# V_FB.net
KiCad netlist of a schematic drawn in Altium Designer
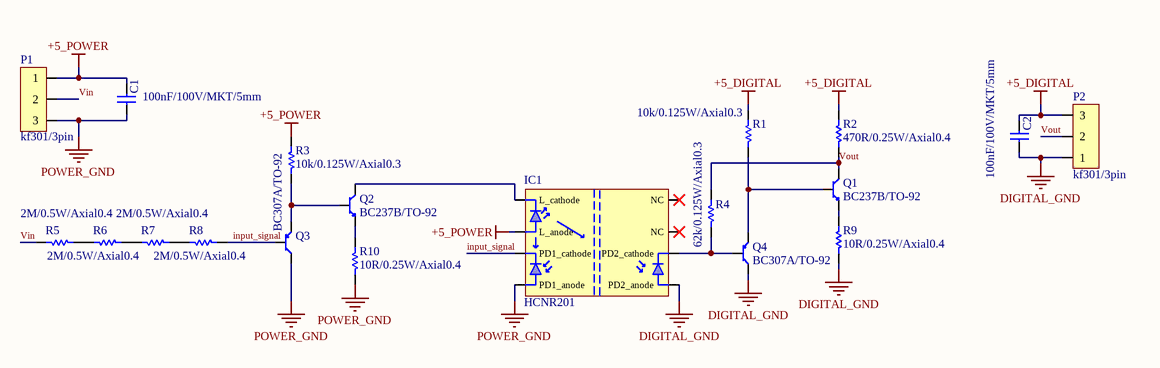
[diagram p0: V_FB.SchDoc]

(export (version "E")
  (design (tool "Eeschema 10.0.6"))
  (components
    (comp (ref "C1")
      (value "100nF/100V/MKT/5mm")
      (footprint "mkt 5mm")
      (description "Capacitor")
      (libsource (lib "Schlib") (part "Capacitor"))
    )
    (comp (ref "C2")
      (value "100nF/100V/MKT/5mm")
      (footprint "mkt 5mm")
      (description "Capacitor")
      (libsource (lib "Schlib") (part "Capacitor"))
    )
    (comp (ref "IC1")
      (value "HCNR201")
      (footprint "HCNR201_DIP8")
      (description "isolate linear optocoupler")
      (libsource (lib "Schlib1") (part "HCNR201"))
    )
    (comp (ref "P1")
      (value "kf301/3pin")
      (footprint "kf301/3pin")
      (description "RELAY")
      (fields (field (name "PUBLISHER") "Altium Limited"))
      (libsource (lib "") (part "kf301/3pin_1"))
    )
    (comp (ref "P2")
      (value "kf301/3pin")
      (footprint "kf301/3pin")
      (description "RELAY")
      (fields (field (name "PUBLISHER") "Altium Limited"))
      (libsource (lib "Schlib1") (part "kf301/3pin"))
    )
    (comp (ref "Q1")
      (value "BC237B/TO-92")
      (footprint "TO-92")
      (description "npn")
      (libsource (lib "Schlib1") (part "BC237B"))
    )
    (comp (ref "Q2")
      (value "BC237B/TO-92")
      (footprint "TO-92")
      (description "npn")
      (libsource (lib "Schlib1") (part "BC237B"))
    )
    (comp (ref "Q3")
      (value "BC307A/TO-92")
      (footprint "TO-92")
      (description "pnp")
      (libsource (lib "Schlib1") (part "BC307A"))
    )
    (comp (ref "Q4")
      (value "BC307A/TO-92")
      (footprint "TO-92")
      (description "pnp")
      (libsource (lib "Schlib1") (part "BC307A"))
    )
    (comp (ref "R1")
      (value "10k/0.125W/Axial0.3")
      (footprint "Axial 0.3")
      (description "Resistor")
      (fields (field (name "PUBLISHER") "Altium Limited"))
      (libsource (lib "Schlib1") (part "Res"))
    )
    (comp (ref "R2")
      (value "470R/0.25W/Axial0.4")
      (footprint "Axial 0.4")
      (description "Resistor")
      (fields (field (name "PUBLISHER") "Altium Limited"))
      (libsource (lib "Schlib1") (part "Res"))
    )
    (comp (ref "R3")
      (value "10k/0.125W/Axial0.3")
      (footprint "Axial 0.3")
      (description "Resistor")
      (fields (field (name "PUBLISHER") "Altium Limited"))
      (libsource (lib "Schlib1") (part "Res"))
    )
    (comp (ref "R4")
      (value "62k/0.125W/Axial0.3")
      (footprint "Axial 0.3")
      (description "Resistor")
      (fields (field (name "PUBLISHER") "Altium Limited"))
      (libsource (lib "Schlib1") (part "Res"))
    )
    (comp (ref "R5")
      (value "2M/0.5W/Axial0.4")
      (footprint "Axial 0.4")
      (description "Resistor")
      (fields (field (name "PUBLISHER") "Altium Limited"))
      (libsource (lib "Schlib1") (part "Res"))
    )
    (comp (ref "R6")
      (value "2M/0.5W/Axial0.4")
      (footprint "Axial 0.4")
      (description "Resistor")
      (fields (field (name "PUBLISHER") "Altium Limited"))
      (libsource (lib "Schlib1") (part "Res"))
    )
    (comp (ref "R7")
      (value "2M/0.5W/Axial0.4")
      (footprint "Axial 0.4")
      (description "Resistor")
      (fields (field (name "PUBLISHER") "Altium Limited"))
      (libsource (lib "Schlib1") (part "Res"))
    )
    (comp (ref "R8")
      (value "2M/0.5W/Axial0.4")
      (footprint "Axial 0.4")
      (description "Resistor")
      (fields (field (name "PUBLISHER") "Altium Limited"))
      (libsource (lib "Schlib1") (part "Res"))
    )
    (comp (ref "R9")
      (value "10R/0.25W/Axial0.4")
      (footprint "Axial 0.4")
      (description "Resistor")
      (fields (field (name "PUBLISHER") "Altium Limited"))
      (libsource (lib "Schlib1") (part "Res"))
    )
    (comp (ref "R10")
      (value "10R/0.25W/Axial0.4")
      (footprint "Axial 0.4")
      (description "Resistor")
      (fields (field (name "PUBLISHER") "Altium Limited"))
      (libsource (lib "Schlib1") (part "Res"))
    )
  )
  (nets
    (net (code "1") (name "+5_DIGITAL") (class "Default")
      (node (ref "C2") (pin "2") (pinfunction "-_2") (pintype "passive"))
      (node (ref "P2") (pin "3") (pinfunction "3_3") (pintype "passive"))
      (node (ref "R1") (pin "1") (pinfunction "1_1") (pintype "passive"))
      (node (ref "R2") (pin "1") (pinfunction "1_1") (pintype "passive"))
    )
    (net (code "2") (name "+5_POWER") (class "Default")
      (node (ref "C1") (pin "2") (pinfunction "-_2") (pintype "passive"))
      (node (ref "IC1") (pin "2") (pinfunction "L_anode_2") (pintype "passive"))
      (node (ref "P1") (pin "1") (pinfunction "1_1") (pintype "passive"))
      (node (ref "R3") (pin "1") (pinfunction "1_1") (pintype "passive"))
    )
    (net (code "3") (name "/Vin") (class "Default")
      (node (ref "P1") (pin "2") (pinfunction "2_2") (pintype "passive"))
      (node (ref "R5") (pin "1") (pinfunction "1_1") (pintype "passive"))
    )
    (net (code "4") (name "/Vout") (class "Default")
      (node (ref "P2") (pin "2") (pinfunction "2_2") (pintype "passive"))
      (node (ref "Q1") (pin "1") (pinfunction "C_1") (pintype "passive"))
      (node (ref "R2") (pin "2") (pinfunction "2_2") (pintype "passive"))
      (node (ref "R4") (pin "2") (pinfunction "2_2") (pintype "passive"))
    )
    (net (code "5") (name "/input_signal") (class "Default")
      (node (ref "IC1") (pin "3") (pinfunction "PD1_cathode_3") (pintype "passive"))
      (node (ref "Q3") (pin "2") (pinfunction "B_2") (pintype "passive"))
      (node (ref "R8") (pin "2") (pinfunction "2_2") (pintype "passive"))
    )
    (net (code "6") (name "DIGITAL_GND") (class "Default")
      (node (ref "C2") (pin "1") (pinfunction "+_1") (pintype "passive"))
      (node (ref "IC1") (pin "5") (pinfunction "PD2_anode_5") (pintype "passive"))
      (node (ref "P2") (pin "1") (pinfunction "1_1") (pintype "passive"))
      (node (ref "Q4") (pin "1") (pinfunction "C_1") (pintype "passive"))
      (node (ref "R9") (pin "2") (pinfunction "2_2") (pintype "passive"))
    )
    (net (code "7") (name "Net-(IC1-L_cathode)") (class "Default")
      (node (ref "IC1") (pin "1") (pinfunction "L_cathode_1") (pintype "passive"))
      (node (ref "Q2") (pin "1") (pinfunction "C_1") (pintype "passive"))
    )
    (net (code "8") (name "Net-(IC1-PD2_cathode)") (class "Default")
      (node (ref "IC1") (pin "6") (pinfunction "PD2_cathode_6") (pintype "passive"))
      (node (ref "Q4") (pin "2") (pinfunction "B_2") (pintype "passive"))
      (node (ref "R4") (pin "1") (pinfunction "1_1") (pintype "passive"))
    )
    (net (code "9") (name "Net-(Q1-B)") (class "Default")
      (node (ref "Q1") (pin "2") (pinfunction "B_2") (pintype "passive"))
      (node (ref "Q4") (pin "3") (pinfunction "E_3") (pintype "passive"))
      (node (ref "R1") (pin "2") (pinfunction "2_2") (pintype "passive"))
    )
    (net (code "10") (name "Net-(Q1-E)") (class "Default")
      (node (ref "Q1") (pin "3") (pinfunction "E_3") (pintype "passive"))
      (node (ref "R9") (pin "1") (pinfunction "1_1") (pintype "passive"))
    )
    (net (code "11") (name "Net-(Q2-B)") (class "Default")
      (node (ref "Q2") (pin "2") (pinfunction "B_2") (pintype "passive"))
      (node (ref "Q3") (pin "3") (pinfunction "E_3") (pintype "passive"))
      (node (ref "R3") (pin "2") (pinfunction "2_2") (pintype "passive"))
    )
    (net (code "12") (name "Net-(Q2-E)") (class "Default")
      (node (ref "Q2") (pin "3") (pinfunction "E_3") (pintype "passive"))
      (node (ref "R10") (pin "1") (pinfunction "1_1") (pintype "passive"))
    )
    (net (code "13") (name "Net-(R5-Pad2)") (class "Default")
      (node (ref "R5") (pin "2") (pinfunction "2_2") (pintype "passive"))
      (node (ref "R6") (pin "1") (pinfunction "1_1") (pintype "passive"))
    )
    (net (code "14") (name "Net-(R6-Pad2)") (class "Default")
      (node (ref "R6") (pin "2") (pinfunction "2_2") (pintype "passive"))
      (node (ref "R7") (pin "1") (pinfunction "1_1") (pintype "passive"))
    )
    (net (code "15") (name "Net-(R7-Pad2)") (class "Default")
      (node (ref "R7") (pin "2") (pinfunction "2_2") (pintype "passive"))
      (node (ref "R8") (pin "1") (pinfunction "1_1") (pintype "passive"))
    )
    (net (code "16") (name "POWER_GND") (class "Default")
      (node (ref "C1") (pin "1") (pinfunction "+_1") (pintype "passive"))
      (node (ref "IC1") (pin "4") (pinfunction "PD1_anode_4") (pintype "passive"))
      (node (ref "P1") (pin "3") (pinfunction "3_3") (pintype "passive"))
      (node (ref "Q3") (pin "1") (pinfunction "C_1") (pintype "passive"))
      (node (ref "R10") (pin "2") (pinfunction "2_2") (pintype "passive"))
    )
    (net (code "17") (name "unconnected-(IC1-NC-Pad7)") (class "Default")
      (node (ref "IC1") (pin "7") (pinfunction "NC_7") (pintype "passive+no_connect"))
    )
    (net (code "18") (name "unconnected-(IC1-NC-Pad8)") (class "Default")
      (node (ref "IC1") (pin "8") (pinfunction "NC_8") (pintype "passive+no_connect"))
    )
  )
)
